# BigMuff.net
KiCad netlist of a schematic drawn in EAGLE
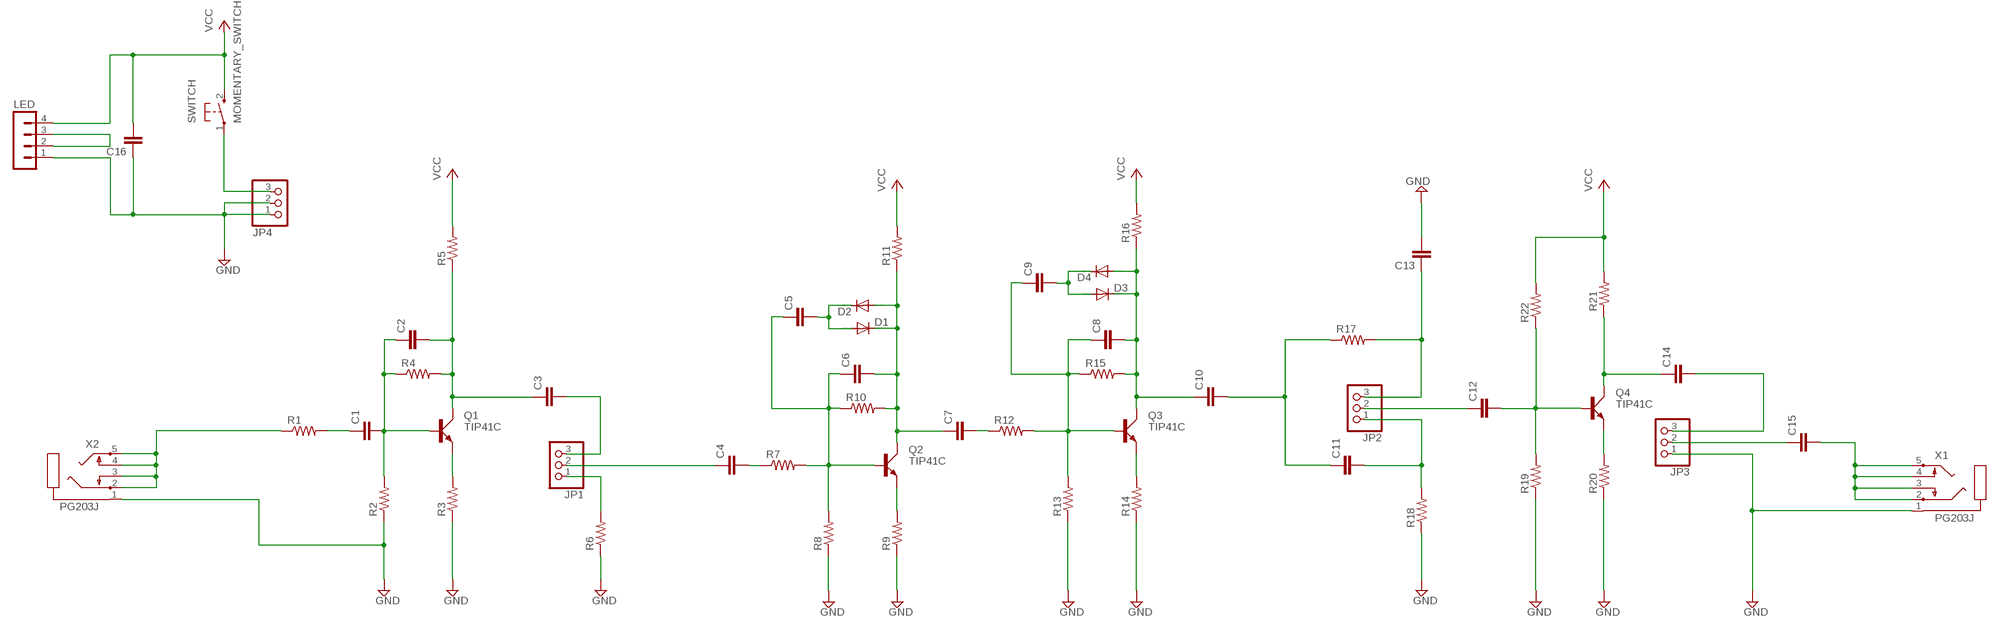
[diagram p0: schematic, sheet 1]

(export (version "E")
  (design (tool "Eeschema 10.0.6"))
  (components
    (comp (ref "C1")
      (value "C2,5-3")
      (footprint "eagle-import:C2.5-3")
      (libsource (lib "eagle-import") (part "C2,5-3"))
    )
    (comp (ref "C2")
      (value "C2,5-3")
      (footprint "eagle-import:C2.5-3")
      (libsource (lib "eagle-import") (part "C2,5-3"))
    )
    (comp (ref "C3")
      (value "C2,5-3")
      (footprint "eagle-import:C2.5-3")
      (libsource (lib "eagle-import") (part "C2,5-3"))
    )
    (comp (ref "C4")
      (value "C2,5-3")
      (footprint "eagle-import:C2.5-3")
      (libsource (lib "eagle-import") (part "C2,5-3"))
    )
    (comp (ref "C5")
      (value "C2,5-3")
      (footprint "eagle-import:C2.5-3")
      (libsource (lib "eagle-import") (part "C2,5-3"))
    )
    (comp (ref "C6")
      (value "C2,5-3")
      (footprint "eagle-import:C2.5-3")
      (libsource (lib "eagle-import") (part "C2,5-3"))
    )
    (comp (ref "C7")
      (value "C2,5-3")
      (footprint "eagle-import:C2.5-3")
      (libsource (lib "eagle-import") (part "C2,5-3"))
    )
    (comp (ref "C8")
      (value "C2,5-3")
      (footprint "eagle-import:C2.5-3")
      (libsource (lib "eagle-import") (part "C2,5-3"))
    )
    (comp (ref "C9")
      (value "C2,5-3")
      (footprint "eagle-import:C2.5-3")
      (libsource (lib "eagle-import") (part "C2,5-3"))
    )
    (comp (ref "C10")
      (value "C2,5-3")
      (footprint "eagle-import:C2.5-3")
      (libsource (lib "eagle-import") (part "C2,5-3"))
    )
    (comp (ref "C11")
      (value "C2,5-3")
      (footprint "eagle-import:C2.5-3")
      (libsource (lib "eagle-import") (part "C2,5-3"))
    )
    (comp (ref "C12")
      (value "C2,5-3")
      (footprint "eagle-import:C2.5-3")
      (libsource (lib "eagle-import") (part "C2,5-3"))
    )
    (comp (ref "C13")
      (value "C2,5-3")
      (footprint "eagle-import:C2.5-3")
      (libsource (lib "eagle-import") (part "C2,5-3"))
    )
    (comp (ref "C14")
      (value "C2,5-3")
      (footprint "eagle-import:C2.5-3")
      (libsource (lib "eagle-import") (part "C2,5-3"))
    )
    (comp (ref "C15")
      (value "C2,5-3")
      (footprint "eagle-import:C2.5-3")
      (libsource (lib "eagle-import") (part "C2,5-3"))
    )
    (comp (ref "C16")
      (value "C2,5-3")
      (footprint "eagle-import:C2.5-3")
      (libsource (lib "eagle-import") (part "C2,5-3"))
    )
    (comp (ref "D1")
      (value "DIODE-D-2.5")
      (footprint "eagle-import:D-2.5")
      (libsource (lib "eagle-import") (part "DIODE-D-2.5"))
    )
    (comp (ref "D2")
      (value "DIODE-D-2.5")
      (footprint "eagle-import:D-2.5")
      (libsource (lib "eagle-import") (part "DIODE-D-2.5"))
    )
    (comp (ref "D3")
      (value "DIODE-D-2.5")
      (footprint "eagle-import:D-2.5")
      (libsource (lib "eagle-import") (part "DIODE-D-2.5"))
    )
    (comp (ref "D4")
      (value "DIODE-D-2.5")
      (footprint "eagle-import:D-2.5")
      (libsource (lib "eagle-import") (part "DIODE-D-2.5"))
    )
    (comp (ref "JP1")
      (value "PINHD-1X3")
      (footprint "eagle-import:1X03")
      (libsource (lib "eagle-import") (part "PINHD-1X3"))
    )
    (comp (ref "JP2")
      (value "PINHD-1X3")
      (footprint "eagle-import:1X03")
      (libsource (lib "eagle-import") (part "PINHD-1X3"))
    )
    (comp (ref "JP3")
      (value "PINHD-1X3")
      (footprint "eagle-import:1X03")
      (libsource (lib "eagle-import") (part "PINHD-1X3"))
    )
    (comp (ref "JP4")
      (value "PINHD-1X3")
      (footprint "eagle-import:1X03")
      (libsource (lib "eagle-import") (part "PINHD-1X3"))
    )
    (comp (ref "LED")
      (value "MA04-1")
      (footprint "eagle-import:MA04-1")
      (libsource (lib "eagle-import") (part "MA04-1"))
    )
    (comp (ref "Q1")
      (value "TIP41C")
      (footprint "eagle-import:TO220AV")
      (libsource (lib "eagle-import") (part "TIP41C"))
    )
    (comp (ref "Q2")
      (value "TIP41C")
      (footprint "eagle-import:TO220AV")
      (libsource (lib "eagle-import") (part "TIP41C"))
    )
    (comp (ref "Q3")
      (value "TIP41C")
      (footprint "eagle-import:TO220AV")
      (libsource (lib "eagle-import") (part "TIP41C"))
    )
    (comp (ref "Q4")
      (value "TIP41C")
      (footprint "eagle-import:TO220AV")
      (libsource (lib "eagle-import") (part "TIP41C"))
    )
    (comp (ref "R1")
      (value "R-US_0204/2V")
      (footprint "eagle-import:0204V")
      (libsource (lib "eagle-import") (part "R-US_0204/2V"))
    )
    (comp (ref "R2")
      (value "R-US_0204/2V")
      (footprint "eagle-import:0204V")
      (libsource (lib "eagle-import") (part "R-US_0204/2V"))
    )
    (comp (ref "R3")
      (value "R-US_0204/2V")
      (footprint "eagle-import:0204V")
      (libsource (lib "eagle-import") (part "R-US_0204/2V"))
    )
    (comp (ref "R4")
      (value "R-US_0204/2V")
      (footprint "eagle-import:0204V")
      (libsource (lib "eagle-import") (part "R-US_0204/2V"))
    )
    (comp (ref "R5")
      (value "R-US_0204/2V")
      (footprint "eagle-import:0204V")
      (libsource (lib "eagle-import") (part "R-US_0204/2V"))
    )
    (comp (ref "R6")
      (value "R-US_0204/2V")
      (footprint "eagle-import:0204V")
      (libsource (lib "eagle-import") (part "R-US_0204/2V"))
    )
    (comp (ref "R7")
      (value "R-US_0204/2V")
      (footprint "eagle-import:0204V")
      (libsource (lib "eagle-import") (part "R-US_0204/2V"))
    )
    (comp (ref "R8")
      (value "R-US_0204/2V")
      (footprint "eagle-import:0204V")
      (libsource (lib "eagle-import") (part "R-US_0204/2V"))
    )
    (comp (ref "R9")
      (value "R-US_0204/2V")
      (footprint "eagle-import:0204V")
      (libsource (lib "eagle-import") (part "R-US_0204/2V"))
    )
    (comp (ref "R10")
      (value "R-US_0204/2V")
      (footprint "eagle-import:0204V")
      (libsource (lib "eagle-import") (part "R-US_0204/2V"))
    )
    (comp (ref "R11")
      (value "R-US_0204/2V")
      (footprint "eagle-import:0204V")
      (libsource (lib "eagle-import") (part "R-US_0204/2V"))
    )
    (comp (ref "R12")
      (value "R-US_0204/2V")
      (footprint "eagle-import:0204V")
      (libsource (lib "eagle-import") (part "R-US_0204/2V"))
    )
    (comp (ref "R13")
      (value "R-US_0204/2V")
      (footprint "eagle-import:0204V")
      (libsource (lib "eagle-import") (part "R-US_0204/2V"))
    )
    (comp (ref "R14")
      (value "R-US_0204/2V")
      (footprint "eagle-import:0204V")
      (libsource (lib "eagle-import") (part "R-US_0204/2V"))
    )
    (comp (ref "R15")
      (value "R-US_0204/2V")
      (footprint "eagle-import:0204V")
      (libsource (lib "eagle-import") (part "R-US_0204/2V"))
    )
    (comp (ref "R16")
      (value "R-US_0204/2V")
      (footprint "eagle-import:0204V")
      (libsource (lib "eagle-import") (part "R-US_0204/2V"))
    )
    (comp (ref "R17")
      (value "R-US_0204/2V")
      (footprint "eagle-import:0204V")
      (libsource (lib "eagle-import") (part "R-US_0204/2V"))
    )
    (comp (ref "R18")
      (value "R-US_0204/2V")
      (footprint "eagle-import:0204V")
      (libsource (lib "eagle-import") (part "R-US_0204/2V"))
    )
    (comp (ref "R19")
      (value "R-US_0204/2V")
      (footprint "eagle-import:0204V")
      (libsource (lib "eagle-import") (part "R-US_0204/2V"))
    )
    (comp (ref "R20")
      (value "R-US_0204/2V")
      (footprint "eagle-import:0204V")
      (libsource (lib "eagle-import") (part "R-US_0204/2V"))
    )
    (comp (ref "R21")
      (value "R-US_0204/2V")
      (footprint "eagle-import:0204V")
      (libsource (lib "eagle-import") (part "R-US_0204/2V"))
    )
    (comp (ref "R22")
      (value "R-US_0204/2V")
      (footprint "eagle-import:0204V")
      (libsource (lib "eagle-import") (part "R-US_0204/2V"))
    )
    (comp (ref "SWITCH")
      (value "MOMENTARY_SWITCH")
      (footprint "eagle-import:MOMENTARY_SWITCH")
      (libsource (lib "eagle-import") (part "MOMENTARY_SWITCH"))
    )
    (comp (ref "X1")
      (value "PG203J")
      (footprint "eagle-import:PG203J")
      (libsource (lib "eagle-import") (part "PG203J"))
    )
    (comp (ref "X2")
      (value "PG203J")
      (footprint "eagle-import:PG203J")
      (libsource (lib "eagle-import") (part "PG203J"))
    )
  )
  (nets
    (net (code "1") (name "GND") (class "Default")
      (node (ref "C13") (pin "2") (pinfunction "2_2") (pintype "passive"))
      (node (ref "C16") (pin "1") (pinfunction "1_1") (pintype "passive"))
      (node (ref "JP3") (pin "1") (pinfunction "1_1") (pintype "passive"))
      (node (ref "JP4") (pin "1") (pinfunction "1_1") (pintype "passive"))
      (node (ref "JP4") (pin "2") (pinfunction "2_2") (pintype "passive"))
      (node (ref "LED") (pin "1") (pinfunction "1_1") (pintype "passive"))
      (node (ref "R13") (pin "1") (pinfunction "1_1") (pintype "passive"))
      (node (ref "R14") (pin "1") (pinfunction "1_1") (pintype "passive"))
      (node (ref "R18") (pin "1") (pinfunction "1_1") (pintype "passive"))
      (node (ref "R19") (pin "1") (pinfunction "1_1") (pintype "passive"))
      (node (ref "R2") (pin "1") (pinfunction "1_1") (pintype "passive"))
      (node (ref "R20") (pin "1") (pinfunction "1_1") (pintype "passive"))
      (node (ref "R3") (pin "1") (pinfunction "1_1") (pintype "passive"))
      (node (ref "R6") (pin "1") (pinfunction "1_1") (pintype "passive"))
      (node (ref "R8") (pin "1") (pinfunction "1_1") (pintype "passive"))
      (node (ref "R9") (pin "1") (pinfunction "1_1") (pintype "passive"))
      (node (ref "X1") (pin "1") (pinfunction "1_1") (pintype "passive"))
      (node (ref "X2") (pin "1") (pinfunction "1_1") (pintype "passive"))
    )
    (net (code "2") (name "Net-(C1-Pad1)") (class "Default")
      (node (ref "C1") (pin "1") (pinfunction "1_1") (pintype "passive"))
      (node (ref "R1") (pin "2") (pinfunction "2_2") (pintype "passive"))
    )
    (net (code "3") (name "Net-(C1-Pad2)") (class "Default")
      (node (ref "C1") (pin "2") (pinfunction "2_2") (pintype "passive"))
      (node (ref "C2") (pin "1") (pinfunction "1_1") (pintype "passive"))
      (node (ref "Q1") (pin "B") (pinfunction "B_B") (pintype "passive"))
      (node (ref "R2") (pin "2") (pinfunction "2_2") (pintype "passive"))
      (node (ref "R4") (pin "1") (pinfunction "1_1") (pintype "passive"))
    )
    (net (code "4") (name "Net-(C2-Pad2)") (class "Default")
      (node (ref "C2") (pin "2") (pinfunction "2_2") (pintype "passive"))
      (node (ref "C3") (pin "1") (pinfunction "1_1") (pintype "passive"))
      (node (ref "Q1") (pin "C") (pinfunction "C_C") (pintype "passive"))
      (node (ref "R4") (pin "2") (pinfunction "2_2") (pintype "passive"))
      (node (ref "R5") (pin "1") (pinfunction "1_1") (pintype "passive"))
    )
    (net (code "5") (name "Net-(C3-Pad2)") (class "Default")
      (node (ref "C3") (pin "2") (pinfunction "2_2") (pintype "passive"))
      (node (ref "JP1") (pin "3") (pinfunction "3_3") (pintype "passive"))
    )
    (net (code "6") (name "Net-(C4-Pad1)") (class "Default")
      (node (ref "C4") (pin "1") (pinfunction "1_1") (pintype "passive"))
      (node (ref "JP1") (pin "2") (pinfunction "2_2") (pintype "passive"))
    )
    (net (code "7") (name "Net-(C4-Pad2)") (class "Default")
      (node (ref "C4") (pin "2") (pinfunction "2_2") (pintype "passive"))
      (node (ref "R7") (pin "1") (pinfunction "1_1") (pintype "passive"))
    )
    (net (code "8") (name "Net-(C5-Pad1)") (class "Default")
      (node (ref "C5") (pin "1") (pinfunction "1_1") (pintype "passive"))
      (node (ref "C6") (pin "1") (pinfunction "1_1") (pintype "passive"))
      (node (ref "Q2") (pin "B") (pinfunction "B_B") (pintype "passive"))
      (node (ref "R10") (pin "1") (pinfunction "1_1") (pintype "passive"))
      (node (ref "R7") (pin "2") (pinfunction "2_2") (pintype "passive"))
      (node (ref "R8") (pin "2") (pinfunction "2_2") (pintype "passive"))
    )
    (net (code "9") (name "Net-(C5-Pad2)") (class "Default")
      (node (ref "C5") (pin "2") (pinfunction "2_2") (pintype "passive"))
      (node (ref "D1") (pin "A") (pinfunction "A_A") (pintype "passive"))
      (node (ref "D2") (pin "C") (pinfunction "C_C") (pintype "passive"))
    )
    (net (code "10") (name "Net-(C6-Pad2)") (class "Default")
      (node (ref "C6") (pin "2") (pinfunction "2_2") (pintype "passive"))
      (node (ref "C7") (pin "1") (pinfunction "1_1") (pintype "passive"))
      (node (ref "D1") (pin "C") (pinfunction "C_C") (pintype "passive"))
      (node (ref "D2") (pin "A") (pinfunction "A_A") (pintype "passive"))
      (node (ref "Q2") (pin "C") (pinfunction "C_C") (pintype "passive"))
      (node (ref "R10") (pin "2") (pinfunction "2_2") (pintype "passive"))
      (node (ref "R11") (pin "1") (pinfunction "1_1") (pintype "passive"))
    )
    (net (code "11") (name "Net-(C7-Pad2)") (class "Default")
      (node (ref "C7") (pin "2") (pinfunction "2_2") (pintype "passive"))
      (node (ref "R12") (pin "1") (pinfunction "1_1") (pintype "passive"))
    )
    (net (code "12") (name "Net-(C8-Pad1)") (class "Default")
      (node (ref "C8") (pin "1") (pinfunction "1_1") (pintype "passive"))
      (node (ref "C9") (pin "1") (pinfunction "1_1") (pintype "passive"))
      (node (ref "Q3") (pin "B") (pinfunction "B_B") (pintype "passive"))
      (node (ref "R12") (pin "2") (pinfunction "2_2") (pintype "passive"))
      (node (ref "R13") (pin "2") (pinfunction "2_2") (pintype "passive"))
      (node (ref "R15") (pin "1") (pinfunction "1_1") (pintype "passive"))
    )
    (net (code "13") (name "Net-(C9-Pad2)") (class "Default")
      (node (ref "C9") (pin "2") (pinfunction "2_2") (pintype "passive"))
      (node (ref "D3") (pin "A") (pinfunction "A_A") (pintype "passive"))
      (node (ref "D4") (pin "C") (pinfunction "C_C") (pintype "passive"))
    )
    (net (code "14") (name "Net-(C10-Pad1)") (class "Default")
      (node (ref "C10") (pin "1") (pinfunction "1_1") (pintype "passive"))
      (node (ref "C8") (pin "2") (pinfunction "2_2") (pintype "passive"))
      (node (ref "D3") (pin "C") (pinfunction "C_C") (pintype "passive"))
      (node (ref "D4") (pin "A") (pinfunction "A_A") (pintype "passive"))
      (node (ref "Q3") (pin "C") (pinfunction "C_C") (pintype "passive"))
      (node (ref "R15") (pin "2") (pinfunction "2_2") (pintype "passive"))
      (node (ref "R16") (pin "1") (pinfunction "1_1") (pintype "passive"))
    )
    (net (code "15") (name "Net-(C10-Pad2)") (class "Default")
      (node (ref "C10") (pin "2") (pinfunction "2_2") (pintype "passive"))
      (node (ref "C11") (pin "1") (pinfunction "1_1") (pintype "passive"))
      (node (ref "R17") (pin "1") (pinfunction "1_1") (pintype "passive"))
    )
    (net (code "16") (name "Net-(C11-Pad2)") (class "Default")
      (node (ref "C11") (pin "2") (pinfunction "2_2") (pintype "passive"))
      (node (ref "JP2") (pin "1") (pinfunction "1_1") (pintype "passive"))
      (node (ref "R18") (pin "2") (pinfunction "2_2") (pintype "passive"))
    )
    (net (code "17") (name "Net-(C12-Pad1)") (class "Default")
      (node (ref "C12") (pin "1") (pinfunction "1_1") (pintype "passive"))
      (node (ref "JP2") (pin "2") (pinfunction "2_2") (pintype "passive"))
    )
    (net (code "18") (name "Net-(C12-Pad2)") (class "Default")
      (node (ref "C12") (pin "2") (pinfunction "2_2") (pintype "passive"))
      (node (ref "Q4") (pin "B") (pinfunction "B_B") (pintype "passive"))
      (node (ref "R19") (pin "2") (pinfunction "2_2") (pintype "passive"))
      (node (ref "R22") (pin "1") (pinfunction "1_1") (pintype "passive"))
    )
    (net (code "19") (name "Net-(C13-Pad1)") (class "Default")
      (node (ref "C13") (pin "1") (pinfunction "1_1") (pintype "passive"))
      (node (ref "JP2") (pin "3") (pinfunction "3_3") (pintype "passive"))
      (node (ref "R17") (pin "2") (pinfunction "2_2") (pintype "passive"))
    )
    (net (code "20") (name "Net-(C14-Pad1)") (class "Default")
      (node (ref "C14") (pin "1") (pinfunction "1_1") (pintype "passive"))
      (node (ref "Q4") (pin "C") (pinfunction "C_C") (pintype "passive"))
      (node (ref "R21") (pin "1") (pinfunction "1_1") (pintype "passive"))
    )
    (net (code "21") (name "Net-(C14-Pad2)") (class "Default")
      (node (ref "C14") (pin "2") (pinfunction "2_2") (pintype "passive"))
      (node (ref "JP3") (pin "3") (pinfunction "3_3") (pintype "passive"))
    )
    (net (code "22") (name "Net-(C15-Pad1)") (class "Default")
      (node (ref "C15") (pin "1") (pinfunction "1_1") (pintype "passive"))
      (node (ref "JP3") (pin "2") (pinfunction "2_2") (pintype "passive"))
    )
    (net (code "23") (name "Net-(C15-Pad2)") (class "Default")
      (node (ref "C15") (pin "2") (pinfunction "2_2") (pintype "passive"))
      (node (ref "X1") (pin "2") (pinfunction "2_2") (pintype "passive"))
      (node (ref "X1") (pin "3") (pinfunction "3_3") (pintype "passive"))
      (node (ref "X1") (pin "4") (pinfunction "4_4") (pintype "passive"))
      (node (ref "X1") (pin "5") (pinfunction "5_5") (pintype "passive"))
    )
    (net (code "24") (name "Net-(JP1-Pad1)") (class "Default")
      (node (ref "JP1") (pin "1") (pinfunction "1_1") (pintype "passive"))
      (node (ref "R6") (pin "2") (pinfunction "2_2") (pintype "passive"))
    )
    (net (code "25") (name "Net-(JP4-Pad3)") (class "Default")
      (node (ref "JP4") (pin "3") (pinfunction "3_3") (pintype "passive"))
      (node (ref "SWITCH") (pin "1") (pinfunction "1_1") (pintype "passive"))
    )
    (net (code "26") (name "Net-(LED-Pad2)") (class "Default")
      (node (ref "LED") (pin "2") (pinfunction "2_2") (pintype "passive"))
      (node (ref "LED") (pin "3") (pinfunction "3_3") (pintype "passive"))
    )
    (net (code "27") (name "Net-(Q1-PadE)") (class "Default")
      (node (ref "Q1") (pin "E") (pinfunction "E_E") (pintype "passive"))
      (node (ref "R3") (pin "2") (pinfunction "2_2") (pintype "passive"))
    )
    (net (code "28") (name "Net-(Q2-PadE)") (class "Default")
      (node (ref "Q2") (pin "E") (pinfunction "E_E") (pintype "passive"))
      (node (ref "R9") (pin "2") (pinfunction "2_2") (pintype "passive"))
    )
    (net (code "29") (name "Net-(Q3-PadE)") (class "Default")
      (node (ref "Q3") (pin "E") (pinfunction "E_E") (pintype "passive"))
      (node (ref "R14") (pin "2") (pinfunction "2_2") (pintype "passive"))
    )
    (net (code "30") (name "Net-(Q4-PadE)") (class "Default")
      (node (ref "Q4") (pin "E") (pinfunction "E_E") (pintype "passive"))
      (node (ref "R20") (pin "2") (pinfunction "2_2") (pintype "passive"))
    )
    (net (code "31") (name "Net-(R1-Pad1)") (class "Default")
      (node (ref "R1") (pin "1") (pinfunction "1_1") (pintype "passive"))
      (node (ref "X2") (pin "2") (pinfunction "2_2") (pintype "passive"))
      (node (ref "X2") (pin "3") (pinfunction "3_3") (pintype "passive"))
      (node (ref "X2") (pin "4") (pinfunction "4_4") (pintype "passive"))
      (node (ref "X2") (pin "5") (pinfunction "5_5") (pintype "passive"))
    )
    (net (code "32") (name "VCC") (class "Default")
      (node (ref "C16") (pin "2") (pinfunction "2_2") (pintype "passive"))
      (node (ref "LED") (pin "4") (pinfunction "4_4") (pintype "passive"))
      (node (ref "R11") (pin "2") (pinfunction "2_2") (pintype "passive"))
      (node (ref "R16") (pin "2") (pinfunction "2_2") (pintype "passive"))
      (node (ref "R21") (pin "2") (pinfunction "2_2") (pintype "passive"))
      (node (ref "R22") (pin "2") (pinfunction "2_2") (pintype "passive"))
      (node (ref "R5") (pin "2") (pinfunction "2_2") (pintype "passive"))
      (node (ref "SWITCH") (pin "2") (pinfunction "2_2") (pintype "passive"))
    )
  )
)
